# 05-MUX.net
KiCad netlist of a schematic drawn in Altium Designer
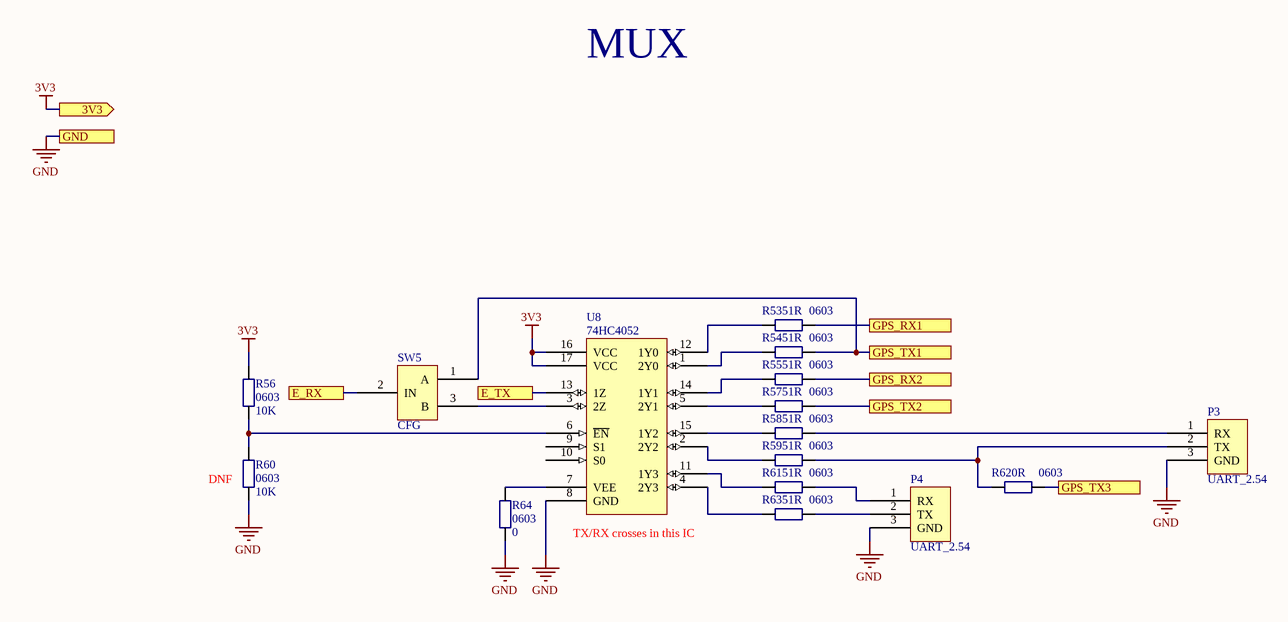
[diagram p0: 05-MUX.SchDoc]

(export (version "E")
  (design (tool "Eeschema 10.0.6"))
  (components
    (comp (ref "P3")
      (value "UART_2.54")
      (footprint "UART_2.54")
      (libsource (lib "ComponentsLib") (part "UART_2.54"))
    )
    (comp (ref "P4")
      (value "UART_2.54")
      (footprint "UART_2.54")
      (libsource (lib "ComponentsLib") (part "UART_2.54"))
    )
    (comp (ref "R53")
      (value "~")
      (footprint "R0604")
      (description "Resistor General")
      (fields (field (name "SIZE") "0603") (field (name "RESISTANCE") "51R"))
      (libsource (lib "ComponentsLib") (part "R_GENERAL"))
    )
    (comp (ref "R54")
      (value "~")
      (footprint "R0604")
      (description "Resistor General")
      (fields (field (name "SIZE") "0603") (field (name "RESISTANCE") "51R"))
      (libsource (lib "ComponentsLib") (part "R_GENERAL"))
    )
    (comp (ref "R55")
      (value "~")
      (footprint "R0604")
      (description "Resistor General")
      (fields (field (name "SIZE") "0603") (field (name "RESISTANCE") "51R"))
      (libsource (lib "ComponentsLib") (part "R_GENERAL"))
    )
    (comp (ref "R56")
      (value "~")
      (footprint "R0604")
      (description "Resistor General")
      (fields (field (name "SIZE") "0603") (field (name "RESISTANCE") "10K"))
      (libsource (lib "ComponentsLib") (part "R_GENERAL"))
    )
    (comp (ref "R57")
      (value "~")
      (footprint "R0604")
      (description "Resistor General")
      (fields (field (name "SIZE") "0603") (field (name "RESISTANCE") "51R"))
      (libsource (lib "ComponentsLib") (part "R_GENERAL"))
    )
    (comp (ref "R58")
      (value "~")
      (footprint "R0604")
      (description "Resistor General")
      (fields (field (name "SIZE") "0603") (field (name "RESISTANCE") "51R"))
      (libsource (lib "ComponentsLib") (part "R_GENERAL"))
    )
    (comp (ref "R59")
      (value "~")
      (footprint "R0604")
      (description "Resistor General")
      (fields (field (name "SIZE") "0603") (field (name "RESISTANCE") "51R"))
      (libsource (lib "ComponentsLib") (part "R_GENERAL"))
    )
    (comp (ref "R60")
      (value "~")
      (footprint "R0604")
      (description "Resistor General")
      (fields (field (name "SIZE") "0603") (field (name "RESISTANCE") "10K"))
      (libsource (lib "ComponentsLib") (part "R_GENERAL"))
    )
    (comp (ref "R61")
      (value "~")
      (footprint "R0604")
      (description "Resistor General")
      (fields (field (name "SIZE") "0603") (field (name "RESISTANCE") "51R"))
      (libsource (lib "ComponentsLib") (part "R_GENERAL"))
    )
    (comp (ref "R62")
      (value "~")
      (footprint "R0604")
      (description "Resistor General")
      (fields (field (name "SIZE") "0603") (field (name "RESISTANCE") "0R"))
      (libsource (lib "ComponentsLib") (part "R_GENERAL"))
    )
    (comp (ref "R63")
      (value "~")
      (footprint "R0604")
      (description "Resistor General")
      (fields (field (name "SIZE") "0603") (field (name "RESISTANCE") "51R"))
      (libsource (lib "ComponentsLib") (part "R_GENERAL"))
    )
    (comp (ref "R64")
      (value "~")
      (footprint "R0604")
      (description "Resistor General")
      (fields (field (name "SIZE") "0603") (field (name "RESISTANCE") "0"))
      (libsource (lib "ComponentsLib") (part "R_GENERAL"))
    )
    (comp (ref "SW5") (value "CFG") (footprint "CFG_0603") (libsource (lib "ComponentsLib") (part "CFG")))
    (comp (ref "U8")
      (value "74HC4052")
      (footprint "TSSOP16-SOP65P637X110-17N")
      (description "Dual 4-channel analog multiplexer/demultiplexer")
      (fields (field (name "MP") "74HC4052PW") (field (name "MF") "NXP"))
      (libsource (lib "ComponentsLib") (part "74HC4052"))
    )
  )
  (nets
    (net (code "1") (name "/E_RX") (class "Default")
      (node (ref "SW5") (pin "2") (pinfunction "IN_2") (pintype "passive"))
    )
    (net (code "2") (name "/E_TX") (class "Default")
      (node (ref "U8") (pin "13") (pinfunction "1Z_13") (pintype "bidirectional"))
    )
    (net (code "3") (name "/GPS_RX1") (class "Default")
      (node (ref "R53") (pin "2") (pinfunction "2_2") (pintype "passive"))
    )
    (net (code "4") (name "/GPS_RX2") (class "Default")
      (node (ref "R55") (pin "2") (pinfunction "2_2") (pintype "passive"))
    )
    (net (code "5") (name "/GPS_TX1") (class "Default")
      (node (ref "R54") (pin "2") (pinfunction "2_2") (pintype "passive"))
      (node (ref "SW5") (pin "1") (pinfunction "A_1") (pintype "passive"))
    )
    (net (code "6") (name "/GPS_TX2") (class "Default")
      (node (ref "R57") (pin "2") (pinfunction "2_2") (pintype "passive"))
    )
    (net (code "7") (name "/GPS_TX3") (class "Default")
      (node (ref "R62") (pin "2") (pinfunction "2_2") (pintype "passive"))
    )
    (net (code "8") (name "3V3") (class "Default")
      (node (ref "R56") (pin "1") (pinfunction "1_1") (pintype "passive"))
      (node (ref "U8") (pin "16") (pinfunction "VCC_16") (pintype "power_in"))
      (node (ref "U8") (pin "17") (pinfunction "VCC_17") (pintype "power_in"))
    )
    (net (code "9") (name "GND") (class "Default")
      (node (ref "P3") (pin "3") (pinfunction "GND_3") (pintype "passive"))
      (node (ref "P4") (pin "3") (pinfunction "GND_3") (pintype "passive"))
      (node (ref "R60") (pin "2") (pinfunction "2_2") (pintype "passive"))
      (node (ref "R64") (pin "1") (pinfunction "1_1") (pintype "passive"))
      (node (ref "U8") (pin "8") (pinfunction "GND_8") (pintype "power_in"))
    )
    (net (code "10") (name "Net-(P3-RX)") (class "Default")
      (node (ref "P3") (pin "1") (pinfunction "RX_1") (pintype "passive"))
      (node (ref "R58") (pin "2") (pinfunction "2_2") (pintype "passive"))
    )
    (net (code "11") (name "Net-(P3-TX)") (class "Default")
      (node (ref "P3") (pin "2") (pinfunction "TX_2") (pintype "passive"))
      (node (ref "R59") (pin "2") (pinfunction "2_2") (pintype "passive"))
      (node (ref "R62") (pin "1") (pinfunction "1_1") (pintype "passive"))
    )
    (net (code "12") (name "Net-(P4-RX)") (class "Default")
      (node (ref "P4") (pin "1") (pinfunction "RX_1") (pintype "passive"))
      (node (ref "R61") (pin "2") (pinfunction "2_2") (pintype "passive"))
    )
    (net (code "13") (name "Net-(P4-TX)") (class "Default")
      (node (ref "P4") (pin "2") (pinfunction "TX_2") (pintype "passive"))
      (node (ref "R63") (pin "2") (pinfunction "2_2") (pintype "passive"))
    )
    (net (code "14") (name "Net-(SW5-B)") (class "Default")
      (node (ref "SW5") (pin "3") (pinfunction "B_3") (pintype "passive"))
      (node (ref "U8") (pin "3") (pinfunction "2Z_3") (pintype "bidirectional"))
    )
    (net (code "15") (name "Net-(U8-1Y0)") (class "Default")
      (node (ref "R53") (pin "1") (pinfunction "1_1") (pintype "passive"))
      (node (ref "U8") (pin "12") (pinfunction "1Y0_12") (pintype "bidirectional"))
    )
    (net (code "16") (name "Net-(U8-1Y1)") (class "Default")
      (node (ref "R55") (pin "1") (pinfunction "1_1") (pintype "passive"))
      (node (ref "U8") (pin "14") (pinfunction "1Y1_14") (pintype "bidirectional"))
    )
    (net (code "17") (name "Net-(U8-1Y2)") (class "Default")
      (node (ref "R58") (pin "1") (pinfunction "1_1") (pintype "passive"))
      (node (ref "U8") (pin "15") (pinfunction "1Y2_15") (pintype "bidirectional"))
    )
    (net (code "18") (name "Net-(U8-1Y3)") (class "Default")
      (node (ref "R61") (pin "1") (pinfunction "1_1") (pintype "passive"))
      (node (ref "U8") (pin "11") (pinfunction "1Y3_11") (pintype "bidirectional"))
    )
    (net (code "19") (name "Net-(U8-2Y0)") (class "Default")
      (node (ref "R54") (pin "1") (pinfunction "1_1") (pintype "passive"))
      (node (ref "U8") (pin "1") (pinfunction "2Y0_1") (pintype "bidirectional"))
    )
    (net (code "20") (name "Net-(U8-2Y1)") (class "Default")
      (node (ref "R57") (pin "1") (pinfunction "1_1") (pintype "passive"))
      (node (ref "U8") (pin "5") (pinfunction "2Y1_5") (pintype "bidirectional"))
    )
    (net (code "21") (name "Net-(U8-2Y2)") (class "Default")
      (node (ref "R59") (pin "1") (pinfunction "1_1") (pintype "passive"))
      (node (ref "U8") (pin "2") (pinfunction "2Y2_2") (pintype "bidirectional"))
    )
    (net (code "22") (name "Net-(U8-2Y3)") (class "Default")
      (node (ref "R63") (pin "1") (pinfunction "1_1") (pintype "passive"))
      (node (ref "U8") (pin "4") (pinfunction "2Y3_4") (pintype "bidirectional"))
    )
    (net (code "23") (name "Net-(U8-VEE)") (class "Default")
      (node (ref "R64") (pin "2") (pinfunction "2_2") (pintype "passive"))
      (node (ref "U8") (pin "7") (pinfunction "VEE_7") (pintype "power_in"))
    )
    (net (code "24") (name "Net-(U8-~{EN})") (class "Default")
      (node (ref "R56") (pin "2") (pinfunction "2_2") (pintype "passive"))
      (node (ref "R60") (pin "1") (pinfunction "1_1") (pintype "passive"))
      (node (ref "U8") (pin "6") (pinfunction "~{EN}_6") (pintype "input"))
    )
    (net (code "25") (name "unconnected-(U8-S0-Pad10)") (class "Default")
      (node (ref "U8") (pin "10") (pinfunction "S0_10") (pintype "input"))
    )
    (net (code "26") (name "unconnected-(U8-S1-Pad9)") (class "Default")
      (node (ref "U8") (pin "9") (pinfunction "S1_9") (pintype "input"))
    )
  )
)
